# odbiornik.net
KiCad netlist of a schematic drawn in EAGLE
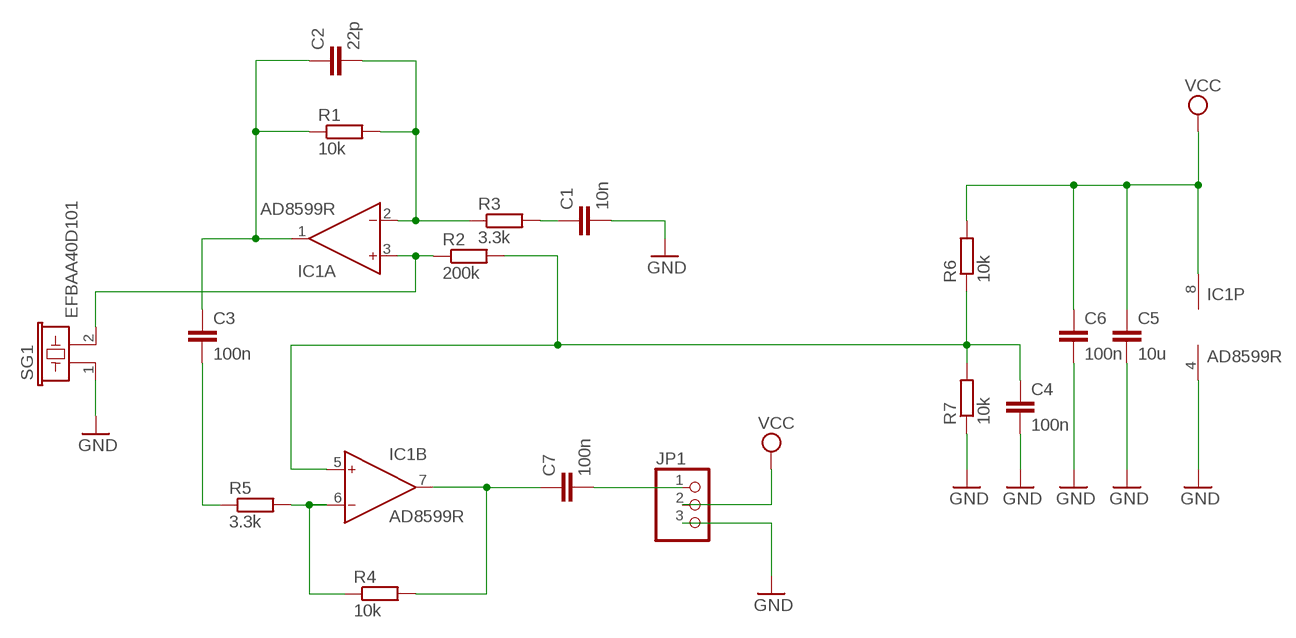
[diagram p0: schematic, sheet 1]

(export (version "E")
  (design (tool "Eeschema 10.0.6"))
  (components
    (comp (ref "C1")
      (value "10n")
      (footprint "eagle-import:C1206K")
      (libsource (lib "eagle-import") (part "C-EUC1206K"))
    )
    (comp (ref "C2")
      (value "22p")
      (footprint "eagle-import:C1206K")
      (libsource (lib "eagle-import") (part "C-EUC1206K"))
    )
    (comp (ref "C3")
      (value "100n")
      (footprint "eagle-import:C1206K")
      (libsource (lib "eagle-import") (part "C-EUC1206K"))
    )
    (comp (ref "C4")
      (value "100n")
      (footprint "eagle-import:C1206K")
      (libsource (lib "eagle-import") (part "C-EUC1206K"))
    )
    (comp (ref "C5")
      (value "10u")
      (footprint "eagle-import:C1206K")
      (libsource (lib "eagle-import") (part "C-EUC1206K"))
    )
    (comp (ref "C6")
      (value "100n")
      (footprint "eagle-import:C1206")
      (libsource (lib "eagle-import") (part "C-EUC1206"))
    )
    (comp (ref "C7")
      (value "100n")
      (footprint "eagle-import:C1206")
      (libsource (lib "eagle-import") (part "C-EUC1206"))
    )
    (comp (ref "IC1")
      (value "AD8599R")
      (footprint "eagle-import:SO8")
      (fields (field (name "MPN") "AD8599ARZ"))
      (libsource (lib "eagle-import") (part "AD8599R"))
    )
    (comp (ref "JP1")
      (value "PINHD-1X3")
      (footprint "eagle-import:1X03")
      (libsource (lib "eagle-import") (part "PINHD-1X3"))
    )
    (comp (ref "R1")
      (value "10k")
      (footprint "eagle-import:R0805")
      (libsource (lib "eagle-import") (part "R-EU_R0805"))
    )
    (comp (ref "R2")
      (value "200k")
      (footprint "eagle-import:R0805")
      (libsource (lib "eagle-import") (part "R-EU_R0805"))
    )
    (comp (ref "R3")
      (value "3.3k")
      (footprint "eagle-import:R0805")
      (libsource (lib "eagle-import") (part "R-EU_R0805"))
    )
    (comp (ref "R4")
      (value "10k")
      (footprint "eagle-import:R0805")
      (libsource (lib "eagle-import") (part "R-EU_R0805"))
    )
    (comp (ref "R5")
      (value "3.3k")
      (footprint "eagle-import:R0805")
      (libsource (lib "eagle-import") (part "R-EU_R0805"))
    )
    (comp (ref "R6")
      (value "10k")
      (footprint "eagle-import:R0805")
      (libsource (lib "eagle-import") (part "R-EU_R0805"))
    )
    (comp (ref "R7")
      (value "10k")
      (footprint "eagle-import:R0805")
      (libsource (lib "eagle-import") (part "R-EU_R0805"))
    )
    (comp (ref "SG1")
      (value "EFBAA40D101")
      (footprint "eagle-import:EFBAA40D101")
      (libsource (lib "eagle-import") (part "EFB?AA40D101"))
    )
  )
  (nets
    (net (code "1") (name "GND") (class "Default")
      (node (ref "C1") (pin "2") (pinfunction "2_2") (pintype "passive"))
      (node (ref "C4") (pin "2") (pinfunction "2_2") (pintype "passive"))
      (node (ref "C5") (pin "2") (pinfunction "2_2") (pintype "passive"))
      (node (ref "C6") (pin "2") (pinfunction "2_2") (pintype "passive"))
      (node (ref "IC1") (pin "4") (pinfunction "V-_4") (pintype "power_in"))
      (node (ref "JP1") (pin "3") (pinfunction "3_3") (pintype "passive"))
      (node (ref "R7") (pin "1") (pinfunction "1_1") (pintype "passive"))
      (node (ref "SG1") (pin "1") (pinfunction "1_1") (pintype "passive"))
    )
    (net (code "2") (name "Net-(C1-Pad1)") (class "Default")
      (node (ref "C1") (pin "1") (pinfunction "1_1") (pintype "passive"))
      (node (ref "R3") (pin "2") (pinfunction "2_2") (pintype "passive"))
    )
    (net (code "3") (name "Net-(C3-Pad2)") (class "Default")
      (node (ref "C3") (pin "2") (pinfunction "2_2") (pintype "passive"))
      (node (ref "R5") (pin "1") (pinfunction "1_1") (pintype "passive"))
    )
    (net (code "4") (name "Net-(C7-Pad2)") (class "Default")
      (node (ref "C7") (pin "2") (pinfunction "2_2") (pintype "passive"))
      (node (ref "JP1") (pin "1") (pinfunction "1_1") (pintype "passive"))
    )
    (net (code "5") (name "Net-(IC1A-IN+)") (class "Default")
      (node (ref "IC1") (pin "3") (pinfunction "IN+_3") (pintype "input"))
      (node (ref "R2") (pin "1") (pinfunction "1_1") (pintype "passive"))
      (node (ref "SG1") (pin "2") (pinfunction "2_2") (pintype "passive"))
    )
    (net (code "6") (name "Net-(IC1A-IN-)") (class "Default")
      (node (ref "C2") (pin "2") (pinfunction "2_2") (pintype "passive"))
      (node (ref "IC1") (pin "2") (pinfunction "IN-_2") (pintype "input"))
      (node (ref "R1") (pin "2") (pinfunction "2_2") (pintype "passive"))
      (node (ref "R3") (pin "1") (pinfunction "1_1") (pintype "passive"))
    )
    (net (code "7") (name "Net-(IC1A-OUT)") (class "Default")
      (node (ref "C2") (pin "1") (pinfunction "1_1") (pintype "passive"))
      (node (ref "C3") (pin "1") (pinfunction "1_1") (pintype "passive"))
      (node (ref "IC1") (pin "1") (pinfunction "OUT_1") (pintype "output"))
      (node (ref "R1") (pin "1") (pinfunction "1_1") (pintype "passive"))
    )
    (net (code "8") (name "Net-(IC1B-IN+)") (class "Default")
      (node (ref "C4") (pin "1") (pinfunction "1_1") (pintype "passive"))
      (node (ref "IC1") (pin "5") (pinfunction "IN+_5") (pintype "input"))
      (node (ref "R2") (pin "2") (pinfunction "2_2") (pintype "passive"))
      (node (ref "R6") (pin "1") (pinfunction "1_1") (pintype "passive"))
      (node (ref "R7") (pin "2") (pinfunction "2_2") (pintype "passive"))
    )
    (net (code "9") (name "Net-(IC1B-IN-)") (class "Default")
      (node (ref "IC1") (pin "6") (pinfunction "IN-_6") (pintype "input"))
      (node (ref "R4") (pin "1") (pinfunction "1_1") (pintype "passive"))
      (node (ref "R5") (pin "2") (pinfunction "2_2") (pintype "passive"))
    )
    (net (code "10") (name "Net-(IC1B-OUT)") (class "Default")
      (node (ref "C7") (pin "1") (pinfunction "1_1") (pintype "passive"))
      (node (ref "IC1") (pin "7") (pinfunction "OUT_7") (pintype "output"))
      (node (ref "R4") (pin "2") (pinfunction "2_2") (pintype "passive"))
    )
    (net (code "11") (name "VCC") (class "Default")
      (node (ref "C5") (pin "1") (pinfunction "1_1") (pintype "passive"))
      (node (ref "C6") (pin "1") (pinfunction "1_1") (pintype "passive"))
      (node (ref "IC1") (pin "8") (pinfunction "V+_8") (pintype "power_in"))
      (node (ref "JP1") (pin "2") (pinfunction "2_2") (pintype "passive"))
      (node (ref "R6") (pin "2") (pinfunction "2_2") (pintype "passive"))
    )
  )
)
